# ssm2166board.net
KiCad netlist of a schematic drawn in EAGLE
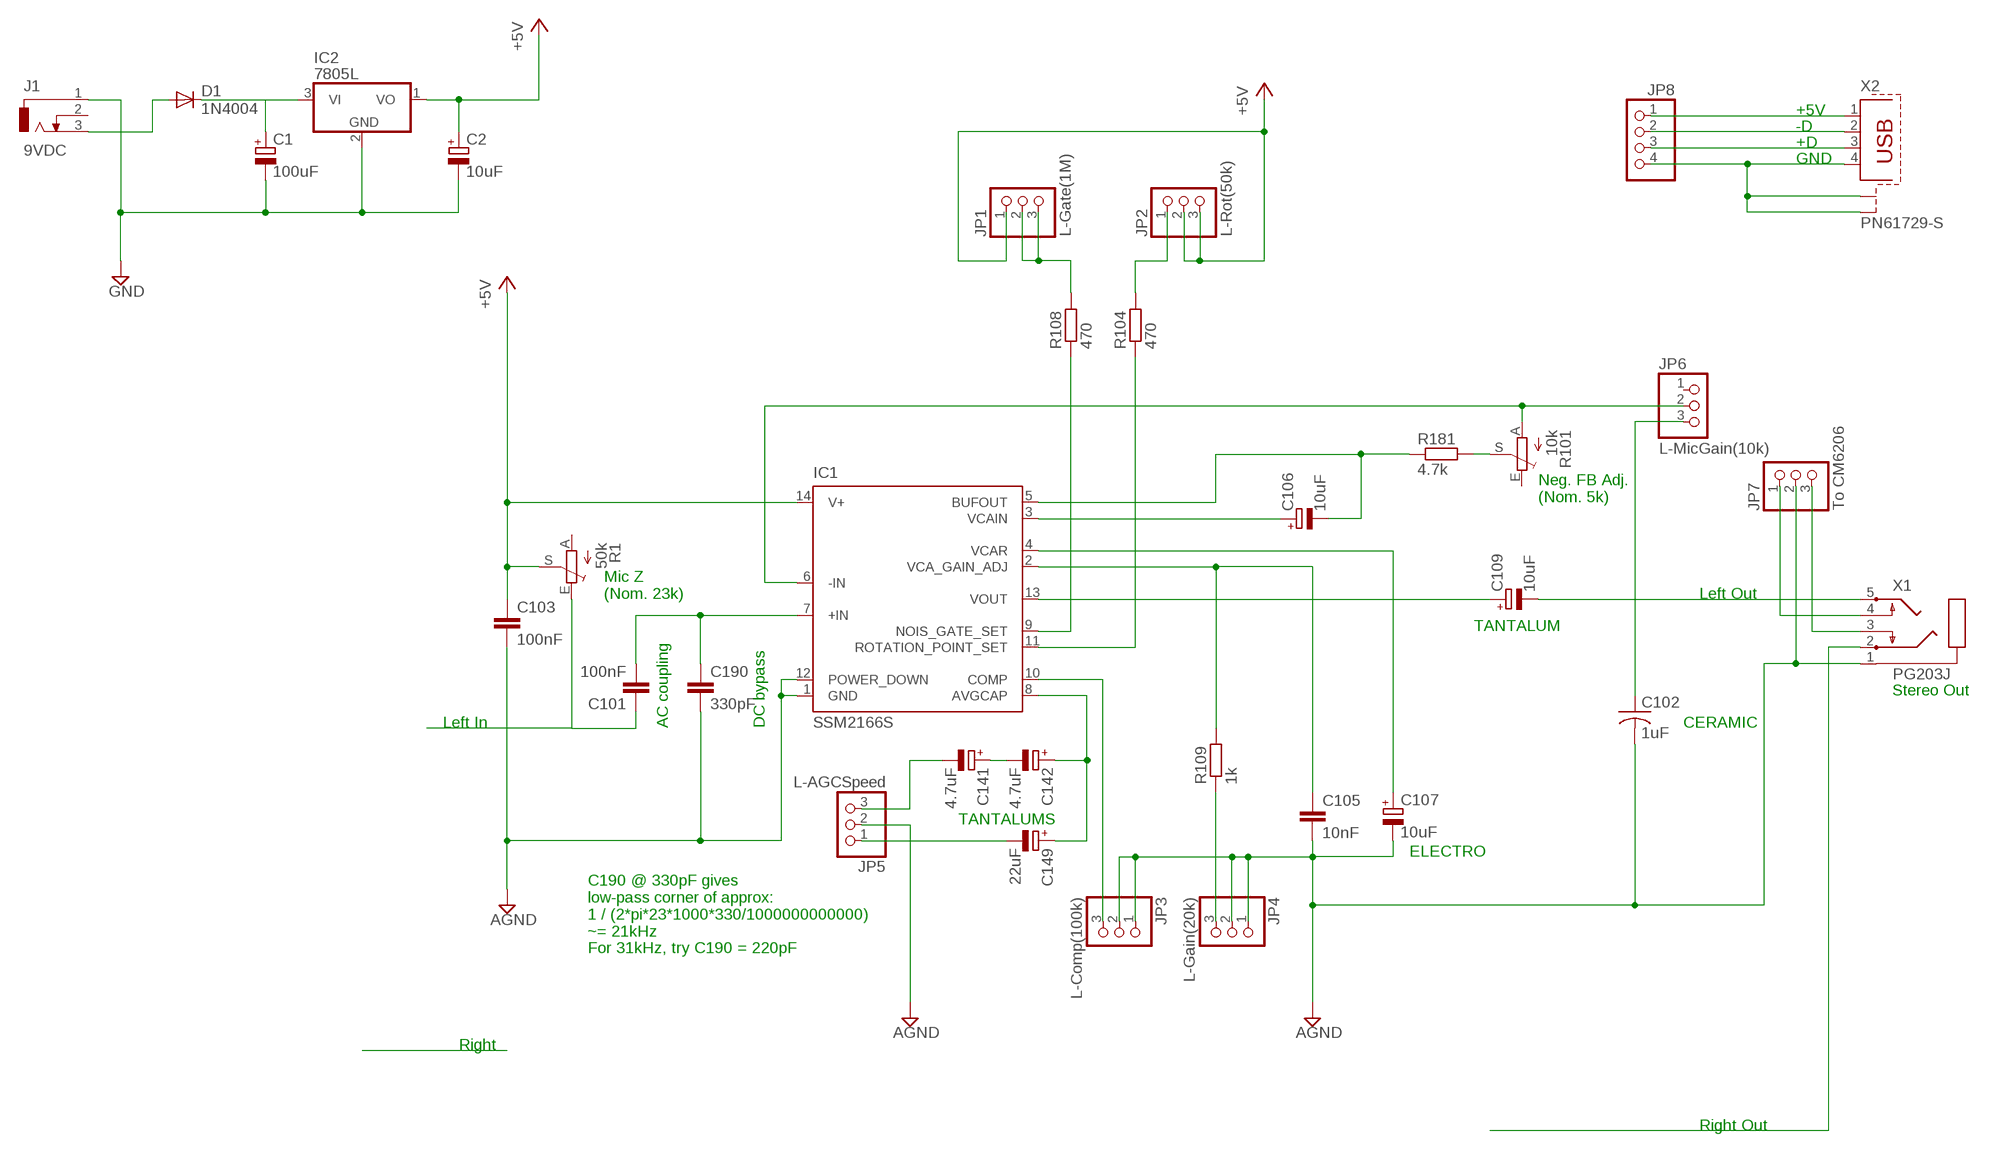
[diagram p0: schematic, sheet 1]

(export (version "E")
  (design (tool "Eeschema 10.0.6"))
  (components
    (comp (ref "C1")
      (value "100uF")
      (footprint "eagle-import:E2-5")
      (libsource (lib "eagle-import") (part "CPOL-EUE2-5"))
    )
    (comp (ref "C2")
      (value "10uF")
      (footprint "eagle-import:E2-5")
      (libsource (lib "eagle-import") (part "CPOL-EUE2-5"))
    )
    (comp (ref "C101")
      (value "100nF")
      (footprint "eagle-import:C1206")
      (libsource (lib "eagle-import") (part "C-EUC1206"))
    )
    (comp (ref "C102")
      (value "1uF")
      (footprint "eagle-import:C2220K")
      (libsource (lib "eagle-import") (part "C-USC2220K"))
    )
    (comp (ref "C103")
      (value "100nF")
      (footprint "eagle-import:C1206")
      (libsource (lib "eagle-import") (part "C-EUC1206"))
    )
    (comp (ref "C105")
      (value "10nF")
      (footprint "eagle-import:C1206")
      (libsource (lib "eagle-import") (part "C-EUC1206"))
    )
    (comp (ref "C106")
      (value "10uF")
      (footprint "eagle-import:E2-5")
      (libsource (lib "eagle-import") (part "CPOL-EUE2-5"))
    )
    (comp (ref "C107")
      (value "10uF")
      (footprint "eagle-import:E2-5")
      (libsource (lib "eagle-import") (part "CPOL-EUE2-5"))
    )
    (comp (ref "C109")
      (value "10uF")
      (footprint "eagle-import:CT6032")
      (libsource (lib "eagle-import") (part "resistor_CPOL-EUCT6032"))
    )
    (comp (ref "C141")
      (value "4.7uF")
      (footprint "eagle-import:CT6032")
      (libsource (lib "eagle-import") (part "resistor_CPOL-EUCT6032"))
    )
    (comp (ref "C142")
      (value "4.7uF")
      (footprint "eagle-import:CT6032")
      (libsource (lib "eagle-import") (part "resistor_CPOL-EUCT6032"))
    )
    (comp (ref "C149")
      (value "22uF")
      (footprint "eagle-import:CT7343")
      (libsource (lib "eagle-import") (part "resistor_CPOL-EUCT7343"))
    )
    (comp (ref "C190")
      (value "330pF")
      (footprint "eagle-import:C1206")
      (libsource (lib "eagle-import") (part "C-EUC1206"))
    )
    (comp (ref "D1")
      (value "1N4004")
      (footprint "eagle-import:DO41-10")
      (libsource (lib "eagle-import") (part "1N4004"))
    )
    (comp (ref "IC1")
      (value "SSM2166S")
      (footprint "eagle-import:SO14")
      (fields (field (name "MF") "ALTERA CORPORATION") (field (name "MPN") "SSM2166S-REEL"))
      (libsource (lib "eagle-import") (part "SSM2166S"))
    )
    (comp (ref "IC2")
      (value "7805L")
      (footprint "eagle-import:TO92")
      (libsource (lib "eagle-import") (part "78L05"))
    )
    (comp (ref "J1")
      (value "9VDC")
      (footprint "eagle-import:DCJ0303")
      (libsource (lib "eagle-import") (part "DCJ0303"))
    )
    (comp (ref "JP1")
      (value "L-Gate(1M)")
      (footprint "eagle-import:1X03")
      (libsource (lib "eagle-import") (part "PINHD-1X3"))
    )
    (comp (ref "JP2")
      (value "L-Rot(50k)")
      (footprint "eagle-import:1X03")
      (libsource (lib "eagle-import") (part "PINHD-1X3"))
    )
    (comp (ref "JP3")
      (value "L-Comp(100k)")
      (footprint "eagle-import:1X03")
      (libsource (lib "eagle-import") (part "PINHD-1X3"))
    )
    (comp (ref "JP4")
      (value "L-Gain(20k)")
      (footprint "eagle-import:1X03")
      (libsource (lib "eagle-import") (part "PINHD-1X3"))
    )
    (comp (ref "JP5")
      (value "L-AGCSpeed")
      (footprint "eagle-import:1X03")
      (libsource (lib "eagle-import") (part "PINHD-1X3"))
    )
    (comp (ref "JP6")
      (value "L-MicGain(10k)")
      (footprint "eagle-import:1X03")
      (libsource (lib "eagle-import") (part "PINHD-1X3"))
    )
    (comp (ref "JP7")
      (value "To CM6206")
      (footprint "eagle-import:1X03")
      (libsource (lib "eagle-import") (part "PINHD-1X3"))
    )
    (comp (ref "JP8")
      (value "PINHD-1X4")
      (footprint "eagle-import:1X04")
      (libsource (lib "eagle-import") (part "PINHD-1X4"))
    )
    (comp (ref "R1")
      (value "50k")
      (footprint "eagle-import:CA6V")
      (libsource (lib "eagle-import") (part "TRIM_EU-CA6V"))
    )
    (comp (ref "R101")
      (value "10k")
      (footprint "eagle-import:CA6V")
      (libsource (lib "eagle-import") (part "TRIM_EU-CA6V"))
    )
    (comp (ref "R104")
      (value "470")
      (footprint "eagle-import:R1206")
      (libsource (lib "eagle-import") (part "R-EU_R1206"))
    )
    (comp (ref "R108")
      (value "470")
      (footprint "eagle-import:R1206")
      (libsource (lib "eagle-import") (part "R-EU_R1206"))
    )
    (comp (ref "R109")
      (value "1k")
      (footprint "eagle-import:R1206")
      (libsource (lib "eagle-import") (part "R-EU_R1206"))
    )
    (comp (ref "R181")
      (value "4.7k")
      (footprint "eagle-import:R1206")
      (libsource (lib "eagle-import") (part "R-EU_R1206"))
    )
    (comp (ref "X1")
      (value "PG203J")
      (footprint "eagle-import:PG203J")
      (libsource (lib "eagle-import") (part "PG203J"))
    )
    (comp (ref "X2")
      (value "PN61729-S")
      (footprint "eagle-import:PN61729-S")
      (libsource (lib "eagle-import") (part "PN61729-S"))
    )
  )
  (nets
    (net (code "1") (name "+5V") (class "Default")
      (node (ref "C103") (pin "1") (pinfunction "1_1") (pintype "passive"))
      (node (ref "C2") (pin "+") (pinfunction "+_+") (pintype "passive"))
      (node (ref "IC1") (pin "14") (pinfunction "V+_14") (pintype "power_in"))
      (node (ref "IC2") (pin "1") (pinfunction "VO_1") (pintype "passive"))
      (node (ref "JP1") (pin "1") (pinfunction "1_1") (pintype "passive"))
      (node (ref "JP2") (pin "2") (pinfunction "2_2") (pintype "passive"))
      (node (ref "JP2") (pin "3") (pinfunction "3_3") (pintype "passive"))
      (node (ref "R1") (pin "S") (pinfunction "S_S") (pintype "passive"))
    )
    (net (code "2") (name "AGND") (class "Default")
      (node (ref "C102") (pin "2") (pinfunction "2_2") (pintype "passive"))
      (node (ref "C103") (pin "2") (pinfunction "2_2") (pintype "passive"))
      (node (ref "C105") (pin "2") (pinfunction "2_2") (pintype "passive"))
      (node (ref "C107") (pin "-") (pinfunction "-_-") (pintype "passive"))
      (node (ref "C190") (pin "2") (pinfunction "2_2") (pintype "passive"))
      (node (ref "IC1") (pin "1") (pinfunction "GND_1") (pintype "power_in"))
      (node (ref "IC1") (pin "12") (pinfunction "POWER_DOWN_12") (pintype "input"))
      (node (ref "JP3") (pin "1") (pinfunction "1_1") (pintype "passive"))
      (node (ref "JP3") (pin "2") (pinfunction "2_2") (pintype "passive"))
      (node (ref "JP4") (pin "1") (pinfunction "1_1") (pintype "passive"))
      (node (ref "JP4") (pin "2") (pinfunction "2_2") (pintype "passive"))
      (node (ref "JP5") (pin "2") (pinfunction "2_2") (pintype "passive"))
      (node (ref "JP7") (pin "2") (pinfunction "2_2") (pintype "passive"))
      (node (ref "X1") (pin "1") (pinfunction "1_1") (pintype "passive"))
    )
    (net (code "3") (name "GND") (class "Default")
      (node (ref "C1") (pin "-") (pinfunction "-_-") (pintype "passive"))
      (node (ref "C2") (pin "-") (pinfunction "-_-") (pintype "passive"))
      (node (ref "IC2") (pin "2") (pinfunction "GND_2") (pintype "passive"))
      (node (ref "J1") (pin "1") (pinfunction "1_1") (pintype "passive"))
    )
    (net (code "4") (name "Net-(C101-Pad1)") (class "Default")
      (node (ref "C101") (pin "1") (pinfunction "1_1") (pintype "passive"))
      (node (ref "R1") (pin "E") (pinfunction "E_E") (pintype "passive"))
    )
    (net (code "5") (name "Net-(C102-Pad1)") (class "Default")
      (node (ref "C102") (pin "1") (pinfunction "1_1") (pintype "passive"))
      (node (ref "JP6") (pin "3") (pinfunction "3_3") (pintype "passive"))
    )
    (net (code "6") (name "Net-(C109-Pad-)") (class "Default")
      (node (ref "C109") (pin "-") (pinfunction "-_-") (pintype "passive"))
      (node (ref "X1") (pin "5") (pinfunction "5_5") (pintype "passive"))
    )
    (net (code "7") (name "Net-(C141-Pad+)") (class "Default")
      (node (ref "C141") (pin "+") (pinfunction "+_+") (pintype "passive"))
      (node (ref "C142") (pin "-") (pinfunction "-_-") (pintype "passive"))
    )
    (net (code "8") (name "Net-(C141-Pad-)") (class "Default")
      (node (ref "C141") (pin "-") (pinfunction "-_-") (pintype "passive"))
      (node (ref "JP5") (pin "3") (pinfunction "3_3") (pintype "passive"))
    )
    (net (code "9") (name "Net-(C149-Pad-)") (class "Default")
      (node (ref "C149") (pin "-") (pinfunction "-_-") (pintype "passive"))
      (node (ref "JP5") (pin "1") (pinfunction "1_1") (pintype "passive"))
    )
    (net (code "10") (name "Net-(D1-PadA)") (class "Default")
      (node (ref "D1") (pin "A") (pinfunction "A_A") (pintype "passive"))
      (node (ref "J1") (pin "3") (pinfunction "3_3") (pintype "passive"))
    )
    (net (code "11") (name "Net-(IC1-+IN)") (class "Default")
      (node (ref "C101") (pin "2") (pinfunction "2_2") (pintype "passive"))
      (node (ref "C190") (pin "1") (pinfunction "1_1") (pintype "passive"))
      (node (ref "IC1") (pin "7") (pinfunction "+IN_7") (pintype "input"))
    )
    (net (code "12") (name "Net-(IC1--IN)") (class "Default")
      (node (ref "IC1") (pin "6") (pinfunction "-IN_6") (pintype "input"))
      (node (ref "JP6") (pin "2") (pinfunction "2_2") (pintype "passive"))
      (node (ref "R101") (pin "A") (pinfunction "A_A") (pintype "passive"))
    )
    (net (code "13") (name "Net-(IC1-AVGCAP)") (class "Default")
      (node (ref "C142") (pin "+") (pinfunction "+_+") (pintype "passive"))
      (node (ref "C149") (pin "+") (pinfunction "+_+") (pintype "passive"))
      (node (ref "IC1") (pin "8") (pinfunction "AVGCAP_8") (pintype "passive"))
    )
    (net (code "14") (name "Net-(IC1-BUFOUT)") (class "Default")
      (node (ref "C106") (pin "-") (pinfunction "-_-") (pintype "passive"))
      (node (ref "IC1") (pin "5") (pinfunction "BUFOUT_5") (pintype "output"))
      (node (ref "R181") (pin "1") (pinfunction "1_1") (pintype "passive"))
    )
    (net (code "15") (name "Net-(IC1-COMP)") (class "Default")
      (node (ref "IC1") (pin "10") (pinfunction "COMP_10") (pintype "passive"))
      (node (ref "JP3") (pin "3") (pinfunction "3_3") (pintype "passive"))
    )
    (net (code "16") (name "Net-(IC1-NOIS_GATE_SET)") (class "Default")
      (node (ref "IC1") (pin "9") (pinfunction "NOIS_GATE_SET_9") (pintype "passive"))
      (node (ref "R108") (pin "1") (pinfunction "1_1") (pintype "passive"))
    )
    (net (code "17") (name "Net-(IC1-ROTATION_POINT_SET)") (class "Default")
      (node (ref "IC1") (pin "11") (pinfunction "ROTATION_POINT_SET_11") (pintype "passive"))
      (node (ref "R104") (pin "1") (pinfunction "1_1") (pintype "passive"))
    )
    (net (code "18") (name "Net-(IC1-VCAIN)") (class "Default")
      (node (ref "C106") (pin "+") (pinfunction "+_+") (pintype "passive"))
      (node (ref "IC1") (pin "3") (pinfunction "VCAIN_3") (pintype "input"))
    )
    (net (code "19") (name "Net-(IC1-VCAR)") (class "Default")
      (node (ref "C107") (pin "+") (pinfunction "+_+") (pintype "passive"))
      (node (ref "IC1") (pin "4") (pinfunction "VCAR_4") (pintype "input"))
    )
    (net (code "20") (name "Net-(IC1-VCA_GAIN_ADJ)") (class "Default")
      (node (ref "C105") (pin "1") (pinfunction "1_1") (pintype "passive"))
      (node (ref "IC1") (pin "2") (pinfunction "VCA_GAIN_ADJ_2") (pintype "input"))
      (node (ref "R109") (pin "2") (pinfunction "2_2") (pintype "passive"))
    )
    (net (code "21") (name "Net-(IC1-VOUT)") (class "Default")
      (node (ref "C109") (pin "+") (pinfunction "+_+") (pintype "passive"))
      (node (ref "IC1") (pin "13") (pinfunction "VOUT_13") (pintype "output"))
    )
    (net (code "22") (name "Net-(IC2-VI)") (class "Default")
      (node (ref "C1") (pin "+") (pinfunction "+_+") (pintype "passive"))
      (node (ref "D1") (pin "C") (pinfunction "C_C") (pintype "passive"))
      (node (ref "IC2") (pin "3") (pinfunction "VI_3") (pintype "input"))
    )
    (net (code "23") (name "Net-(JP1-Pad2)") (class "Default")
      (node (ref "JP1") (pin "2") (pinfunction "2_2") (pintype "passive"))
      (node (ref "JP1") (pin "3") (pinfunction "3_3") (pintype "passive"))
      (node (ref "R108") (pin "2") (pinfunction "2_2") (pintype "passive"))
    )
    (net (code "24") (name "Net-(JP2-Pad1)") (class "Default")
      (node (ref "JP2") (pin "1") (pinfunction "1_1") (pintype "passive"))
      (node (ref "R104") (pin "2") (pinfunction "2_2") (pintype "passive"))
    )
    (net (code "25") (name "Net-(JP4-Pad3)") (class "Default")
      (node (ref "JP4") (pin "3") (pinfunction "3_3") (pintype "passive"))
      (node (ref "R109") (pin "1") (pinfunction "1_1") (pintype "passive"))
    )
    (net (code "26") (name "Net-(JP7-Pad1)") (class "Default")
      (node (ref "JP7") (pin "1") (pinfunction "1_1") (pintype "passive"))
      (node (ref "X1") (pin "4") (pinfunction "4_4") (pintype "passive"))
    )
    (net (code "27") (name "Net-(JP7-Pad3)") (class "Default")
      (node (ref "JP7") (pin "3") (pinfunction "3_3") (pintype "passive"))
      (node (ref "X1") (pin "3") (pinfunction "3_3") (pintype "passive"))
    )
    (net (code "28") (name "Net-(JP8-Pad1)") (class "Default")
      (node (ref "JP8") (pin "1") (pinfunction "1_1") (pintype "passive"))
      (node (ref "X2") (pin "1") (pinfunction "1_1") (pintype "passive"))
    )
    (net (code "29") (name "Net-(JP8-Pad2)") (class "Default")
      (node (ref "JP8") (pin "2") (pinfunction "2_2") (pintype "passive"))
      (node (ref "X2") (pin "2") (pinfunction "2_2") (pintype "passive"))
    )
    (net (code "30") (name "Net-(JP8-Pad3)") (class "Default")
      (node (ref "JP8") (pin "3") (pinfunction "3_3") (pintype "passive"))
      (node (ref "X2") (pin "3") (pinfunction "3_3") (pintype "passive"))
    )
    (net (code "31") (name "Net-(JP8-Pad4)") (class "Default")
      (node (ref "JP8") (pin "4") (pinfunction "4_4") (pintype "passive"))
      (node (ref "X2") (pin "4") (pinfunction "4_4") (pintype "passive"))
      (node (ref "X2") (pin "S1") (pinfunction "S1_S1") (pintype "passive"))
      (node (ref "X2") (pin "S2") (pinfunction "S2_S2") (pintype "passive"))
    )
    (net (code "32") (name "Net-(R101-PadS)") (class "Default")
      (node (ref "R101") (pin "S") (pinfunction "S_S") (pintype "passive"))
      (node (ref "R181") (pin "2") (pinfunction "2_2") (pintype "passive"))
    )
    (net (code "33") (name "unconnected-(J1-Pad2)") (class "Default")
      (node (ref "J1") (pin "2") (pinfunction "2_2") (pintype "passive"))
    )
    (net (code "34") (name "unconnected-(JP6-Pad1)") (class "Default")
      (node (ref "JP6") (pin "1") (pinfunction "1_1") (pintype "passive"))
    )
    (net (code "35") (name "unconnected-(R1-PadA)") (class "Default")
      (node (ref "R1") (pin "A") (pinfunction "A_A") (pintype "passive"))
    )
    (net (code "36") (name "unconnected-(R101-PadE)") (class "Default")
      (node (ref "R101") (pin "E") (pinfunction "E_E") (pintype "passive"))
    )
    (net (code "37") (name "unconnected-(X1-Pad2)") (class "Default")
      (node (ref "X1") (pin "2") (pinfunction "2_2") (pintype "passive"))
    )
  )
)
